# MCU.net
KiCad netlist of a schematic drawn in Altium Designer
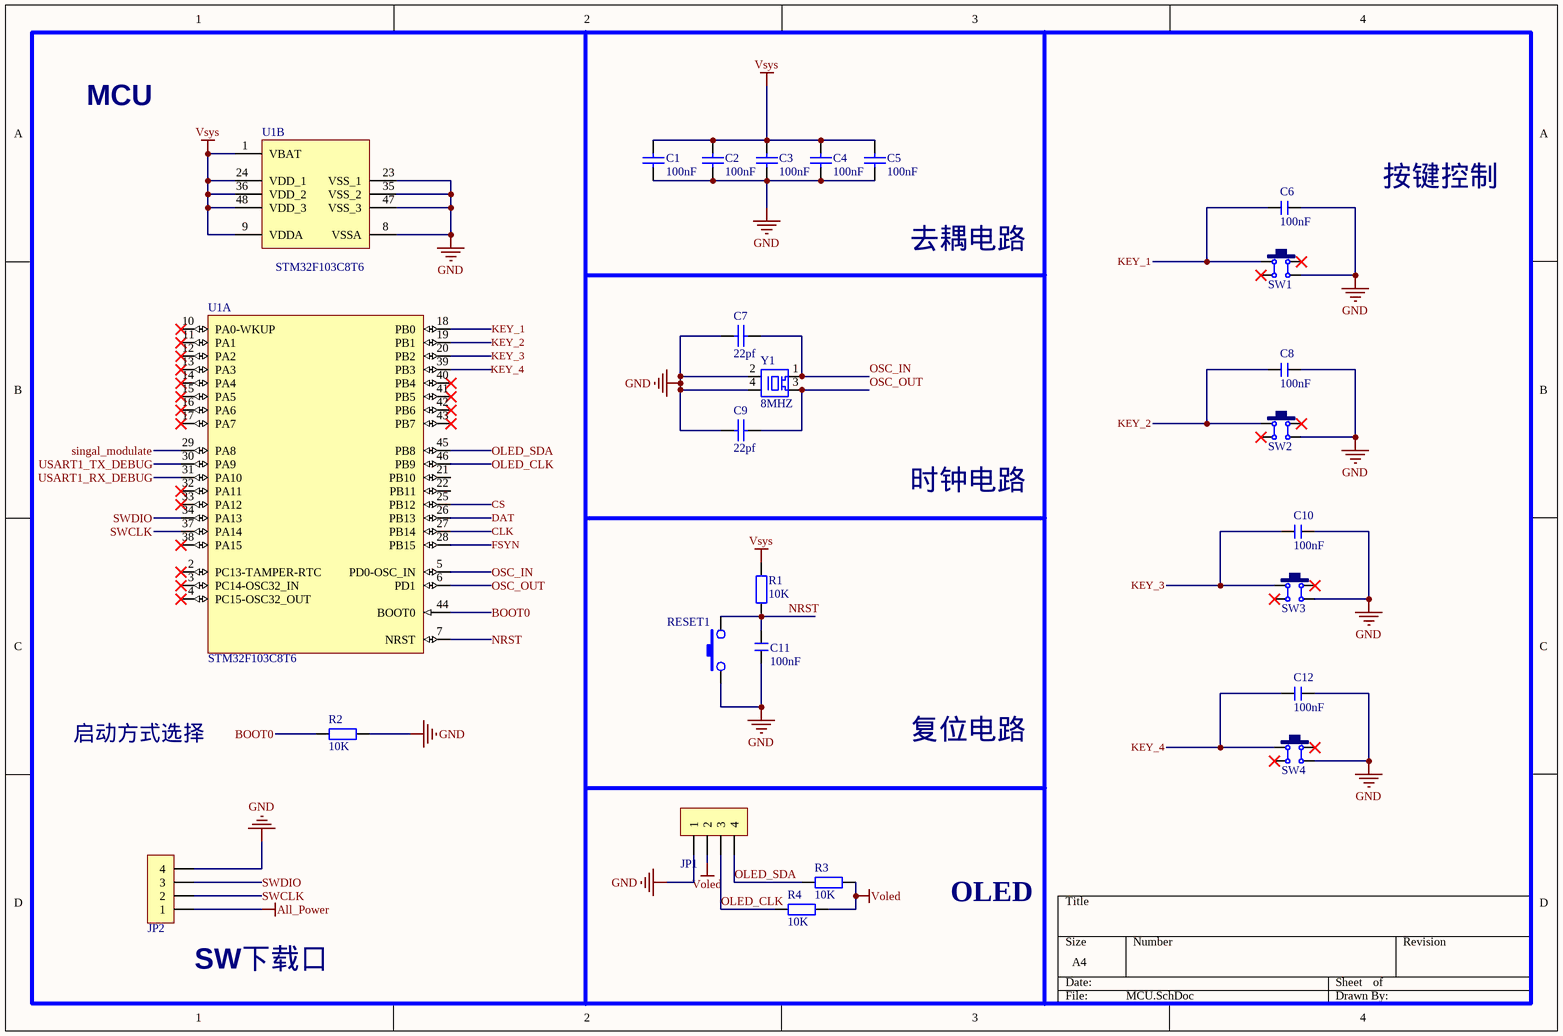
[diagram p0: MCU.SchDoc]

(export (version "E")
  (design (tool "Eeschema 10.0.6"))
  (components
    (comp (ref "C1")
      (value "100nF")
      (footprint "C0603_M")
      (description "贴片电容/MLCC电容")
      (libsource (lib "0.1 - 电阻-电容-电感-保险丝-晶振-晶体-磁珠-电位器-法拉电容-馈通电容") (part "C"))
    )
    (comp (ref "C2")
      (value "100nF")
      (footprint "C0603_M")
      (description "贴片电容/MLCC电容")
      (libsource (lib "0.1 - 电阻-电容-电感-保险丝-晶振-晶体-磁珠-电位器-法拉电容-馈通电容") (part "C"))
    )
    (comp (ref "C3")
      (value "100nF")
      (footprint "C0603_M")
      (description "贴片电容/MLCC电容")
      (libsource (lib "0.1 - 电阻-电容-电感-保险丝-晶振-晶体-磁珠-电位器-法拉电容-馈通电容") (part "C"))
    )
    (comp (ref "C4")
      (value "100nF")
      (footprint "C0603_M")
      (description "贴片电容/MLCC电容")
      (libsource (lib "0.1 - 电阻-电容-电感-保险丝-晶振-晶体-磁珠-电位器-法拉电容-馈通电容") (part "C"))
    )
    (comp (ref "C5")
      (value "100nF")
      (footprint "C0603_M")
      (description "贴片电容/MLCC电容")
      (libsource (lib "0.1 - 电阻-电容-电感-保险丝-晶振-晶体-磁珠-电位器-法拉电容-馈通电容") (part "C"))
    )
    (comp (ref "C6")
      (value "100nF")
      (footprint "C0603_M")
      (description "贴片电容")
      (libsource (lib "0.1 - 电阻-电容-电感") (part "C"))
    )
    (comp (ref "C7")
      (value "22pf")
      (footprint "C0603_M")
      (description "贴片电容")
      (libsource (lib "cdud开发板") (part "C"))
    )
    (comp (ref "C8")
      (value "100nF")
      (footprint "C0603_M")
      (description "贴片电容")
      (libsource (lib "0.1 - 电阻-电容-电感") (part "C"))
    )
    (comp (ref "C9")
      (value "22pf")
      (footprint "C0603_M")
      (description "贴片电容")
      (libsource (lib "cdud开发板") (part "C"))
    )
    (comp (ref "C10")
      (value "100nF")
      (footprint "C0603_M")
      (description "贴片电容")
      (libsource (lib "0.1 - 电阻-电容-电感") (part "C"))
    )
    (comp (ref "C11")
      (value "100nF")
      (footprint "C0603_M")
      (description "无极性贴片电容")
      (fields (field (name "版权归属") "源创客"))
      (libsource (lib "AllSystem") (part "C"))
    )
    (comp (ref "C12")
      (value "100nF")
      (footprint "C0603_M")
      (description "贴片电容")
      (libsource (lib "0.1 - 电阻-电容-电感") (part "C"))
    )
    (comp (ref "JP1")
      (value "HDR-1X4")
      (footprint "HDR2.54-M-LI-4P")
      (description "4P接插件")
      (libsource (lib "") (part "Header 4_1"))
    )
    (comp (ref "JP2")
      (value "HDR-1X4")
      (footprint "HDR2.54-WI-4P")
      (description "4P接插件")
      (libsource (lib "5.5 - 2.54mm(100mil)连接器(XH2.54)") (part "Header 4"))
    )
    (comp (ref "R1")
      (value "10K")
      (footprint "R0603_M")
      (description "贴片电阻")
      (fields (field (name "版权归属") "源创客"))
      (libsource (lib "AllSystem") (part "R"))
    )
    (comp (ref "R2")
      (value "10K")
      (footprint "R0603_M")
      (description "贴片电阻")
      (libsource (lib "cdud开发板") (part "R"))
    )
    (comp (ref "R3")
      (value "10K")
      (footprint "R0603_M")
      (description "贴片电阻")
      (libsource (lib "cdud开发板") (part "R_1"))
    )
    (comp (ref "R4")
      (value "10K")
      (footprint "R0603_M")
      (description "贴片电阻")
      (libsource (lib "cdud开发板") (part "R_1"))
    )
    (comp (ref "RESET1") (value "KEY") (footprint "SW SMD-3*6*4.3") (libsource (lib "STM32") (part "KEY")))
    (comp (ref "SW1")
      (value "12x12x5")
      (footprint "SW SMD-6*6*5")
      (description "贴片12x12轻触开关")
      (fields (field (name "版权归属") "封装库来自淘宝 ID：黄晶宝石"))
      (libsource (lib "0.7 - 常用按键-开关") (part "TSW SMD-12x12"))
    )
    (comp (ref "SW2")
      (value "12x12x5")
      (footprint "SW SMD-6*6*5")
      (description "贴片12x12轻触开关")
      (fields (field (name "版权归属") "封装库来自淘宝 ID：黄晶宝石"))
      (libsource (lib "0.7 - 常用按键-开关") (part "TSW SMD-12x12"))
    )
    (comp (ref "SW3")
      (value "12x12x5")
      (footprint "SW SMD-6*6*5")
      (description "贴片12x12轻触开关")
      (fields (field (name "版权归属") "封装库来自淘宝 ID：黄晶宝石"))
      (libsource (lib "0.7 - 常用按键-开关") (part "TSW SMD-12x12"))
    )
    (comp (ref "SW4")
      (value "12x12x5")
      (footprint "SW SMD-6*6*5")
      (description "贴片12x12轻触开关")
      (fields (field (name "版权归属") "封装库来自淘宝 ID：黄晶宝石"))
      (libsource (lib "0.7 - 常用按键-开关") (part "TSW SMD-12x12"))
    )
    (comp (ref "U1")
      (value "STM32F103C8T6")
      (footprint "LQFP48_N")
      (libsource (lib "2.3 - STM32 F1系列单片机") (part "STM32F103C8T6"))
    )
    (comp (ref "Y1") (value "8MHZ") (footprint "OSC 3225-4P") (libsource (lib "cdud开发板") (part "jinzheng")))
  )
  (nets
    (net (code "1") (name "/BOOT0") (class "Default")
      (node (ref "R2") (pin "1") (pinfunction "1_1") (pintype "passive"))
      (node (ref "U1") (pin "44") (pinfunction "BOOT0_44") (pintype "input"))
    )
    (net (code "2") (name "/CLK") (class "Default")
      (node (ref "U1") (pin "27") (pinfunction "PB14_27") (pintype "bidirectional"))
    )
    (net (code "3") (name "/CS") (class "Default")
      (node (ref "U1") (pin "25") (pinfunction "PB12_25") (pintype "bidirectional"))
    )
    (net (code "4") (name "/DAT") (class "Default")
      (node (ref "U1") (pin "26") (pinfunction "PB13_26") (pintype "bidirectional"))
    )
    (net (code "5") (name "/FSYN") (class "Default")
      (node (ref "U1") (pin "28") (pinfunction "PB15_28") (pintype "bidirectional"))
    )
    (net (code "6") (name "/KEY_1") (class "Default")
      (node (ref "C6") (pin "1") (pinfunction "1_1") (pintype "passive"))
      (node (ref "SW1") (pin "1") (pinfunction "1_1") (pintype "passive"))
      (node (ref "U1") (pin "18") (pinfunction "PB0_18") (pintype "bidirectional"))
    )
    (net (code "7") (name "/KEY_2") (class "Default")
      (node (ref "C8") (pin "1") (pinfunction "1_1") (pintype "passive"))
      (node (ref "SW2") (pin "1") (pinfunction "1_1") (pintype "passive"))
      (node (ref "U1") (pin "19") (pinfunction "PB1_19") (pintype "bidirectional"))
    )
    (net (code "8") (name "/KEY_3") (class "Default")
      (node (ref "C10") (pin "1") (pinfunction "1_1") (pintype "passive"))
      (node (ref "SW3") (pin "1") (pinfunction "1_1") (pintype "passive"))
      (node (ref "U1") (pin "20") (pinfunction "PB2_20") (pintype "bidirectional"))
    )
    (net (code "9") (name "/KEY_4") (class "Default")
      (node (ref "C12") (pin "1") (pinfunction "1_1") (pintype "passive"))
      (node (ref "SW4") (pin "1") (pinfunction "1_1") (pintype "passive"))
      (node (ref "U1") (pin "39") (pinfunction "PB3_39") (pintype "bidirectional"))
    )
    (net (code "10") (name "/NRST") (class "Default")
      (node (ref "C11") (pin "1") (pinfunction "1_1") (pintype "passive"))
      (node (ref "R1") (pin "1") (pinfunction "1_1") (pintype "passive"))
      (node (ref "RESET1") (pin "2") (pinfunction "2_2") (pintype "passive"))
      (node (ref "U1") (pin "7") (pinfunction "NRST_7") (pintype "bidirectional"))
    )
    (net (code "11") (name "/OLED_CLK") (class "Default")
      (node (ref "JP1") (pin "3") (pinfunction "3_3") (pintype "passive"))
      (node (ref "R4") (pin "1") (pinfunction "1_1") (pintype "passive"))
      (node (ref "U1") (pin "46") (pinfunction "PB9_46") (pintype "bidirectional"))
    )
    (net (code "12") (name "/OLED_SDA") (class "Default")
      (node (ref "JP1") (pin "4") (pinfunction "4_4") (pintype "passive"))
      (node (ref "R3") (pin "1") (pinfunction "1_1") (pintype "passive"))
      (node (ref "U1") (pin "45") (pinfunction "PB8_45") (pintype "bidirectional"))
    )
    (net (code "13") (name "/OSC_IN") (class "Default")
      (node (ref "C7") (pin "2") (pinfunction "2_2") (pintype "passive"))
      (node (ref "U1") (pin "5") (pinfunction "PD0-OSC_IN_5") (pintype "bidirectional"))
      (node (ref "Y1") (pin "1") (pinfunction "XTAL1_1") (pintype "passive"))
    )
    (net (code "14") (name "/OSC_OUT") (class "Default")
      (node (ref "C9") (pin "2") (pinfunction "2_2") (pintype "passive"))
      (node (ref "U1") (pin "6") (pinfunction "PD1_6") (pintype "bidirectional"))
      (node (ref "Y1") (pin "3") (pinfunction "XTAL3_3") (pintype "passive"))
    )
    (net (code "15") (name "/SWCLK") (class "Default")
      (node (ref "JP2") (pin "2") (pinfunction "2_2") (pintype "passive"))
      (node (ref "U1") (pin "37") (pinfunction "PA14_37") (pintype "bidirectional"))
    )
    (net (code "16") (name "/SWDIO") (class "Default")
      (node (ref "JP2") (pin "3") (pinfunction "3_3") (pintype "passive"))
      (node (ref "U1") (pin "34") (pinfunction "PA13_34") (pintype "bidirectional"))
    )
    (net (code "17") (name "/USART1_RX_DEBUG") (class "Default")
      (node (ref "U1") (pin "31") (pinfunction "PA10_31") (pintype "bidirectional"))
    )
    (net (code "18") (name "/USART1_TX_DEBUG") (class "Default")
      (node (ref "U1") (pin "30") (pinfunction "PA9_30") (pintype "bidirectional"))
    )
    (net (code "19") (name "/singal_modulate") (class "Default")
      (node (ref "U1") (pin "29") (pinfunction "PA8_29") (pintype "bidirectional"))
    )
    (net (code "20") (name "All_Power") (class "Default")
      (node (ref "JP2") (pin "1") (pinfunction "1_1") (pintype "passive"))
    )
    (net (code "21") (name "GND") (class "Default")
      (node (ref "C1") (pin "1") (pinfunction "1_1") (pintype "passive"))
      (node (ref "C10") (pin "2") (pinfunction "2_2") (pintype "passive"))
      (node (ref "C11") (pin "2") (pinfunction "2_2") (pintype "passive"))
      (node (ref "C12") (pin "2") (pinfunction "2_2") (pintype "passive"))
      (node (ref "C2") (pin "1") (pinfunction "1_1") (pintype "passive"))
      (node (ref "C3") (pin "1") (pinfunction "1_1") (pintype "passive"))
      (node (ref "C4") (pin "1") (pinfunction "1_1") (pintype "passive"))
      (node (ref "C5") (pin "1") (pinfunction "1_1") (pintype "passive"))
      (node (ref "C6") (pin "2") (pinfunction "2_2") (pintype "passive"))
      (node (ref "C7") (pin "1") (pinfunction "1_1") (pintype "passive"))
      (node (ref "C8") (pin "2") (pinfunction "2_2") (pintype "passive"))
      (node (ref "C9") (pin "1") (pinfunction "1_1") (pintype "passive"))
      (node (ref "JP1") (pin "1") (pinfunction "1_1") (pintype "passive"))
      (node (ref "JP2") (pin "4") (pinfunction "4_4") (pintype "passive"))
      (node (ref "R2") (pin "2") (pinfunction "2_2") (pintype "passive"))
      (node (ref "RESET1") (pin "1") (pinfunction "1_1") (pintype "passive"))
      (node (ref "SW1") (pin "3") (pinfunction "3_3") (pintype "passive"))
      (node (ref "SW2") (pin "3") (pinfunction "3_3") (pintype "passive"))
      (node (ref "SW3") (pin "3") (pinfunction "3_3") (pintype "passive"))
      (node (ref "SW4") (pin "3") (pinfunction "3_3") (pintype "passive"))
      (node (ref "U1") (pin "23") (pinfunction "VSS_1_23") (pintype "power_in"))
      (node (ref "U1") (pin "35") (pinfunction "VSS_2_35") (pintype "power_in"))
      (node (ref "U1") (pin "47") (pinfunction "VSS_3_47") (pintype "power_in"))
      (node (ref "U1") (pin "8") (pinfunction "VSSA_8") (pintype "power_in"))
      (node (ref "Y1") (pin "2") (pinfunction "GND_2") (pintype "passive"))
      (node (ref "Y1") (pin "4") (pinfunction "GND_4") (pintype "passive"))
    )
    (net (code "22") (name "Voled") (class "Default")
      (node (ref "JP1") (pin "2") (pinfunction "2_2") (pintype "passive"))
      (node (ref "R3") (pin "2") (pinfunction "2_2") (pintype "passive"))
      (node (ref "R4") (pin "2") (pinfunction "2_2") (pintype "passive"))
    )
    (net (code "23") (name "Vsys") (class "Default")
      (node (ref "C1") (pin "2") (pinfunction "2_2") (pintype "passive"))
      (node (ref "C2") (pin "2") (pinfunction "2_2") (pintype "passive"))
      (node (ref "C3") (pin "2") (pinfunction "2_2") (pintype "passive"))
      (node (ref "C4") (pin "2") (pinfunction "2_2") (pintype "passive"))
      (node (ref "C5") (pin "2") (pinfunction "2_2") (pintype "passive"))
      (node (ref "R1") (pin "2") (pinfunction "2_2") (pintype "passive"))
      (node (ref "U1") (pin "1") (pinfunction "VBAT_1") (pintype "power_in"))
      (node (ref "U1") (pin "24") (pinfunction "VDD_1_24") (pintype "power_in"))
      (node (ref "U1") (pin "36") (pinfunction "VDD_2_36") (pintype "power_in"))
      (node (ref "U1") (pin "48") (pinfunction "VDD_3_48") (pintype "power_in"))
      (node (ref "U1") (pin "9") (pinfunction "VDDA_9") (pintype "power_in"))
    )
    (net (code "24") (name "unconnected-(SW1-Pad2)") (class "Default")
      (node (ref "SW1") (pin "2") (pinfunction "2_2") (pintype "passive+no_connect"))
    )
    (net (code "25") (name "unconnected-(SW1-Pad4)") (class "Default")
      (node (ref "SW1") (pin "4") (pinfunction "4_4") (pintype "passive+no_connect"))
    )
    (net (code "26") (name "unconnected-(SW2-Pad2)") (class "Default")
      (node (ref "SW2") (pin "2") (pinfunction "2_2") (pintype "passive+no_connect"))
    )
    (net (code "27") (name "unconnected-(SW2-Pad4)") (class "Default")
      (node (ref "SW2") (pin "4") (pinfunction "4_4") (pintype "passive+no_connect"))
    )
    (net (code "28") (name "unconnected-(SW3-Pad2)") (class "Default")
      (node (ref "SW3") (pin "2") (pinfunction "2_2") (pintype "passive+no_connect"))
    )
    (net (code "29") (name "unconnected-(SW3-Pad4)") (class "Default")
      (node (ref "SW3") (pin "4") (pinfunction "4_4") (pintype "passive+no_connect"))
    )
    (net (code "30") (name "unconnected-(SW4-Pad2)") (class "Default")
      (node (ref "SW4") (pin "2") (pinfunction "2_2") (pintype "passive+no_connect"))
    )
    (net (code "31") (name "unconnected-(SW4-Pad4)") (class "Default")
      (node (ref "SW4") (pin "4") (pinfunction "4_4") (pintype "passive+no_connect"))
    )
    (net (code "32") (name "unconnected-(U1A-PA0-WKUP-Pad10)") (class "Default")
      (node (ref "U1") (pin "10") (pinfunction "PA0-WKUP_10") (pintype "bidirectional+no_connect"))
    )
    (net (code "33") (name "unconnected-(U1A-PA1-Pad11)") (class "Default")
      (node (ref "U1") (pin "11") (pinfunction "PA1_11") (pintype "bidirectional+no_connect"))
    )
    (net (code "34") (name "unconnected-(U1A-PA2-Pad12)") (class "Default")
      (node (ref "U1") (pin "12") (pinfunction "PA2_12") (pintype "bidirectional+no_connect"))
    )
    (net (code "35") (name "unconnected-(U1A-PA3-Pad13)") (class "Default")
      (node (ref "U1") (pin "13") (pinfunction "PA3_13") (pintype "bidirectional+no_connect"))
    )
    (net (code "36") (name "unconnected-(U1A-PA4-Pad14)") (class "Default")
      (node (ref "U1") (pin "14") (pinfunction "PA4_14") (pintype "bidirectional+no_connect"))
    )
    (net (code "37") (name "unconnected-(U1A-PA5-Pad15)") (class "Default")
      (node (ref "U1") (pin "15") (pinfunction "PA5_15") (pintype "bidirectional+no_connect"))
    )
    (net (code "38") (name "unconnected-(U1A-PA6-Pad16)") (class "Default")
      (node (ref "U1") (pin "16") (pinfunction "PA6_16") (pintype "bidirectional+no_connect"))
    )
    (net (code "39") (name "unconnected-(U1A-PA7-Pad17)") (class "Default")
      (node (ref "U1") (pin "17") (pinfunction "PA7_17") (pintype "bidirectional+no_connect"))
    )
    (net (code "40") (name "unconnected-(U1A-PA11-Pad32)") (class "Default")
      (node (ref "U1") (pin "32") (pinfunction "PA11_32") (pintype "bidirectional+no_connect"))
    )
    (net (code "41") (name "unconnected-(U1A-PA12-Pad33)") (class "Default")
      (node (ref "U1") (pin "33") (pinfunction "PA12_33") (pintype "bidirectional+no_connect"))
    )
    (net (code "42") (name "unconnected-(U1A-PA15-Pad38)") (class "Default")
      (node (ref "U1") (pin "38") (pinfunction "PA15_38") (pintype "bidirectional+no_connect"))
    )
    (net (code "43") (name "unconnected-(U1A-PB4-Pad40)") (class "Default")
      (node (ref "U1") (pin "40") (pinfunction "PB4_40") (pintype "bidirectional+no_connect"))
    )
    (net (code "44") (name "unconnected-(U1A-PB5-Pad41)") (class "Default")
      (node (ref "U1") (pin "41") (pinfunction "PB5_41") (pintype "bidirectional+no_connect"))
    )
    (net (code "45") (name "unconnected-(U1A-PB6-Pad42)") (class "Default")
      (node (ref "U1") (pin "42") (pinfunction "PB6_42") (pintype "bidirectional+no_connect"))
    )
    (net (code "46") (name "unconnected-(U1A-PB7-Pad43)") (class "Default")
      (node (ref "U1") (pin "43") (pinfunction "PB7_43") (pintype "bidirectional+no_connect"))
    )
    (net (code "47") (name "unconnected-(U1A-PB10-Pad21)") (class "Default")
      (node (ref "U1") (pin "21") (pinfunction "PB10_21") (pintype "bidirectional"))
    )
    (net (code "48") (name "unconnected-(U1A-PB11-Pad22)") (class "Default")
      (node (ref "U1") (pin "22") (pinfunction "PB11_22") (pintype "bidirectional"))
    )
    (net (code "49") (name "unconnected-(U1A-PC13-TAMPER-RTC-Pad2)") (class "Default")
      (node (ref "U1") (pin "2") (pinfunction "PC13-TAMPER-RTC_2") (pintype "bidirectional+no_connect"))
    )
    (net (code "50") (name "unconnected-(U1A-PC14-OSC32_IN-Pad3)") (class "Default")
      (node (ref "U1") (pin "3") (pinfunction "PC14-OSC32_IN_3") (pintype "bidirectional+no_connect"))
    )
    (net (code "51") (name "unconnected-(U1A-PC15-OSC32_OUT-Pad4)") (class "Default")
      (node (ref "U1") (pin "4") (pinfunction "PC15-OSC32_OUT_4") (pintype "bidirectional+no_connect"))
    )
  )
)
